# 1.net
KiCad netlist of a schematic drawn in EAGLE
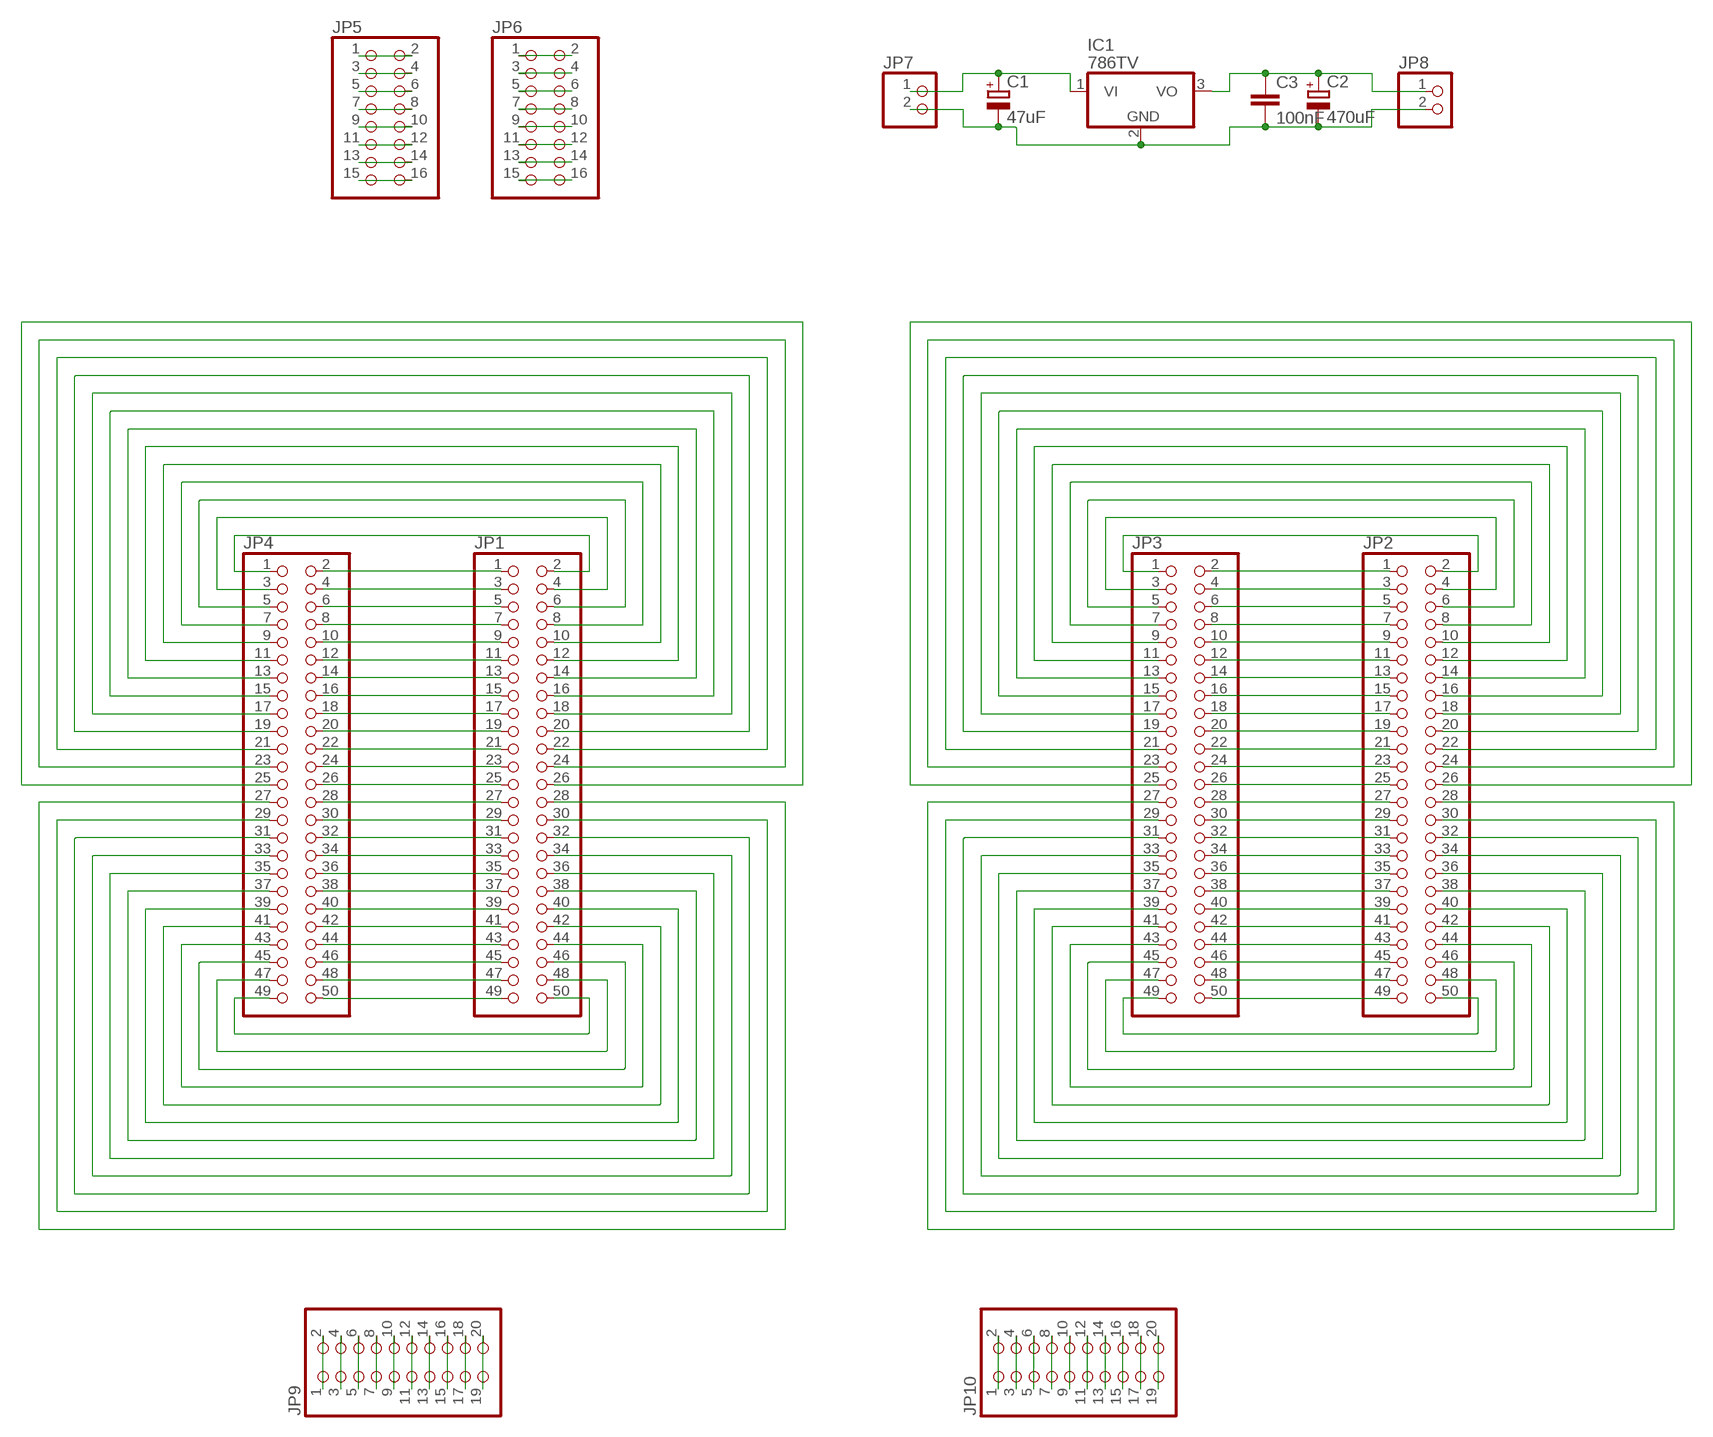
[diagram p0: schematic, sheet 1]

(export (version "E")
  (design (tool "Eeschema 10.0.6"))
  (components
    (comp (ref "C1")
      (value "47uF")
      (footprint "eagle-import:153CLV-0405")
      (libsource (lib "eagle-import") (part "CPOL-EU153CLV-0405"))
    )
    (comp (ref "C2")
      (value "470uF")
      (footprint "eagle-import:153CLV-0405")
      (libsource (lib "eagle-import") (part "CPOL-EU153CLV-0405"))
    )
    (comp (ref "C3")
      (value "100nF")
      (footprint "eagle-import:C025-024X044")
      (libsource (lib "eagle-import") (part "C-EU025-024X044"))
    )
    (comp (ref "IC1")
      (value "786TV")
      (footprint "eagle-import:TO220V")
      (libsource (lib "eagle-import") (part "78TV6"))
    )
    (comp (ref "JP1")
      (value "PINHD-2X25")
      (footprint "eagle-import:2X25")
      (libsource (lib "eagle-import") (part "PINHD-2X25"))
    )
    (comp (ref "JP2")
      (value "PINHD-2X25")
      (footprint "eagle-import:2X25")
      (libsource (lib "eagle-import") (part "PINHD-2X25"))
    )
    (comp (ref "JP3")
      (value "PINHD-2X25")
      (footprint "eagle-import:2X25")
      (libsource (lib "eagle-import") (part "PINHD-2X25"))
    )
    (comp (ref "JP4")
      (value "PINHD-2X25")
      (footprint "eagle-import:2X25")
      (libsource (lib "eagle-import") (part "PINHD-2X25"))
    )
    (comp (ref "JP5")
      (value "PINHD-2X8")
      (footprint "eagle-import:2X08")
      (libsource (lib "eagle-import") (part "PINHD-2X8"))
    )
    (comp (ref "JP6")
      (value "PINHD-2X8")
      (footprint "eagle-import:2X08")
      (libsource (lib "eagle-import") (part "PINHD-2X8"))
    )
    (comp (ref "JP7")
      (value "PINHD-1X2")
      (footprint "eagle-import:1X02")
      (libsource (lib "eagle-import") (part "PINHD-1X2"))
    )
    (comp (ref "JP8")
      (value "PINHD-1X2")
      (footprint "eagle-import:1X02")
      (libsource (lib "eagle-import") (part "PINHD-1X2"))
    )
    (comp (ref "JP9")
      (value "PINHD-2X10")
      (footprint "eagle-import:2X10")
      (libsource (lib "eagle-import") (part "PINHD-2X10"))
    )
    (comp (ref "JP10")
      (value "PINHD-2X10")
      (footprint "eagle-import:2X10")
      (libsource (lib "eagle-import") (part "PINHD-2X10"))
    )
  )
  (nets
    (net (code "1") (name "Net-(IC1-GND)") (class "Default")
      (node (ref "C1") (pin "-") (pinfunction "-_-") (pintype "passive"))
      (node (ref "C2") (pin "-") (pinfunction "-_-") (pintype "passive"))
      (node (ref "C3") (pin "2") (pinfunction "2_2") (pintype "passive"))
      (node (ref "IC1") (pin "2") (pinfunction "GND_2") (pintype "passive"))
      (node (ref "JP7") (pin "2") (pinfunction "2_2") (pintype "passive"))
      (node (ref "JP8") (pin "2") (pinfunction "2_2") (pintype "passive"))
    )
    (net (code "2") (name "Net-(IC1-VI)") (class "Default")
      (node (ref "C1") (pin "+") (pinfunction "+_+") (pintype "passive"))
      (node (ref "IC1") (pin "1") (pinfunction "VI_1") (pintype "input"))
      (node (ref "JP7") (pin "1") (pinfunction "1_1") (pintype "passive"))
    )
    (net (code "3") (name "Net-(IC1-VO)") (class "Default")
      (node (ref "C2") (pin "+") (pinfunction "+_+") (pintype "passive"))
      (node (ref "C3") (pin "1") (pinfunction "1_1") (pintype "passive"))
      (node (ref "IC1") (pin "3") (pinfunction "VO_3") (pintype "passive"))
      (node (ref "JP8") (pin "1") (pinfunction "1_1") (pintype "passive"))
    )
    (net (code "4") (name "Net-(JP1-Pad1)") (class "Default")
      (node (ref "JP1") (pin "1") (pinfunction "1_1") (pintype "passive"))
      (node (ref "JP4") (pin "2") (pinfunction "2_2") (pintype "passive"))
    )
    (net (code "5") (name "Net-(JP1-Pad2)") (class "Default")
      (node (ref "JP1") (pin "2") (pinfunction "2_2") (pintype "passive"))
      (node (ref "JP4") (pin "1") (pinfunction "1_1") (pintype "passive"))
    )
    (net (code "6") (name "Net-(JP1-Pad3)") (class "Default")
      (node (ref "JP1") (pin "3") (pinfunction "3_3") (pintype "passive"))
      (node (ref "JP4") (pin "4") (pinfunction "4_4") (pintype "passive"))
    )
    (net (code "7") (name "Net-(JP1-Pad4)") (class "Default")
      (node (ref "JP1") (pin "4") (pinfunction "4_4") (pintype "passive"))
      (node (ref "JP4") (pin "3") (pinfunction "3_3") (pintype "passive"))
    )
    (net (code "8") (name "Net-(JP1-Pad5)") (class "Default")
      (node (ref "JP1") (pin "5") (pinfunction "5_5") (pintype "passive"))
      (node (ref "JP4") (pin "6") (pinfunction "6_6") (pintype "passive"))
    )
    (net (code "9") (name "Net-(JP1-Pad6)") (class "Default")
      (node (ref "JP1") (pin "6") (pinfunction "6_6") (pintype "passive"))
      (node (ref "JP4") (pin "5") (pinfunction "5_5") (pintype "passive"))
    )
    (net (code "10") (name "Net-(JP1-Pad7)") (class "Default")
      (node (ref "JP1") (pin "7") (pinfunction "7_7") (pintype "passive"))
      (node (ref "JP4") (pin "8") (pinfunction "8_8") (pintype "passive"))
    )
    (net (code "11") (name "Net-(JP1-Pad8)") (class "Default")
      (node (ref "JP1") (pin "8") (pinfunction "8_8") (pintype "passive"))
      (node (ref "JP4") (pin "7") (pinfunction "7_7") (pintype "passive"))
    )
    (net (code "12") (name "Net-(JP1-Pad9)") (class "Default")
      (node (ref "JP1") (pin "9") (pinfunction "9_9") (pintype "passive"))
      (node (ref "JP4") (pin "10") (pinfunction "10_10") (pintype "passive"))
    )
    (net (code "13") (name "Net-(JP1-Pad10)") (class "Default")
      (node (ref "JP1") (pin "10") (pinfunction "10_10") (pintype "passive"))
      (node (ref "JP4") (pin "9") (pinfunction "9_9") (pintype "passive"))
    )
    (net (code "14") (name "Net-(JP1-Pad11)") (class "Default")
      (node (ref "JP1") (pin "11") (pinfunction "11_11") (pintype "passive"))
      (node (ref "JP4") (pin "12") (pinfunction "12_12") (pintype "passive"))
    )
    (net (code "15") (name "Net-(JP1-Pad12)") (class "Default")
      (node (ref "JP1") (pin "12") (pinfunction "12_12") (pintype "passive"))
      (node (ref "JP4") (pin "11") (pinfunction "11_11") (pintype "passive"))
    )
    (net (code "16") (name "Net-(JP1-Pad13)") (class "Default")
      (node (ref "JP1") (pin "13") (pinfunction "13_13") (pintype "passive"))
      (node (ref "JP4") (pin "14") (pinfunction "14_14") (pintype "passive"))
    )
    (net (code "17") (name "Net-(JP1-Pad14)") (class "Default")
      (node (ref "JP1") (pin "14") (pinfunction "14_14") (pintype "passive"))
      (node (ref "JP4") (pin "13") (pinfunction "13_13") (pintype "passive"))
    )
    (net (code "18") (name "Net-(JP1-Pad15)") (class "Default")
      (node (ref "JP1") (pin "15") (pinfunction "15_15") (pintype "passive"))
      (node (ref "JP4") (pin "16") (pinfunction "16_16") (pintype "passive"))
    )
    (net (code "19") (name "Net-(JP1-Pad16)") (class "Default")
      (node (ref "JP1") (pin "16") (pinfunction "16_16") (pintype "passive"))
      (node (ref "JP4") (pin "15") (pinfunction "15_15") (pintype "passive"))
    )
    (net (code "20") (name "Net-(JP1-Pad17)") (class "Default")
      (node (ref "JP1") (pin "17") (pinfunction "17_17") (pintype "passive"))
      (node (ref "JP4") (pin "18") (pinfunction "18_18") (pintype "passive"))
    )
    (net (code "21") (name "Net-(JP1-Pad18)") (class "Default")
      (node (ref "JP1") (pin "18") (pinfunction "18_18") (pintype "passive"))
      (node (ref "JP4") (pin "17") (pinfunction "17_17") (pintype "passive"))
    )
    (net (code "22") (name "Net-(JP1-Pad19)") (class "Default")
      (node (ref "JP1") (pin "19") (pinfunction "19_19") (pintype "passive"))
      (node (ref "JP4") (pin "20") (pinfunction "20_20") (pintype "passive"))
    )
    (net (code "23") (name "Net-(JP1-Pad20)") (class "Default")
      (node (ref "JP1") (pin "20") (pinfunction "20_20") (pintype "passive"))
      (node (ref "JP4") (pin "19") (pinfunction "19_19") (pintype "passive"))
    )
    (net (code "24") (name "Net-(JP1-Pad21)") (class "Default")
      (node (ref "JP1") (pin "21") (pinfunction "21_21") (pintype "passive"))
      (node (ref "JP4") (pin "22") (pinfunction "22_22") (pintype "passive"))
    )
    (net (code "25") (name "Net-(JP1-Pad22)") (class "Default")
      (node (ref "JP1") (pin "22") (pinfunction "22_22") (pintype "passive"))
      (node (ref "JP4") (pin "21") (pinfunction "21_21") (pintype "passive"))
    )
    (net (code "26") (name "Net-(JP1-Pad23)") (class "Default")
      (node (ref "JP1") (pin "23") (pinfunction "23_23") (pintype "passive"))
      (node (ref "JP4") (pin "24") (pinfunction "24_24") (pintype "passive"))
    )
    (net (code "27") (name "Net-(JP1-Pad24)") (class "Default")
      (node (ref "JP1") (pin "24") (pinfunction "24_24") (pintype "passive"))
      (node (ref "JP4") (pin "23") (pinfunction "23_23") (pintype "passive"))
    )
    (net (code "28") (name "Net-(JP1-Pad25)") (class "Default")
      (node (ref "JP1") (pin "25") (pinfunction "25_25") (pintype "passive"))
      (node (ref "JP4") (pin "26") (pinfunction "26_26") (pintype "passive"))
    )
    (net (code "29") (name "Net-(JP1-Pad26)") (class "Default")
      (node (ref "JP1") (pin "26") (pinfunction "26_26") (pintype "passive"))
      (node (ref "JP4") (pin "25") (pinfunction "25_25") (pintype "passive"))
    )
    (net (code "30") (name "Net-(JP1-Pad27)") (class "Default")
      (node (ref "JP1") (pin "27") (pinfunction "27_27") (pintype "passive"))
      (node (ref "JP4") (pin "28") (pinfunction "28_28") (pintype "passive"))
    )
    (net (code "31") (name "Net-(JP1-Pad28)") (class "Default")
      (node (ref "JP1") (pin "28") (pinfunction "28_28") (pintype "passive"))
      (node (ref "JP4") (pin "27") (pinfunction "27_27") (pintype "passive"))
    )
    (net (code "32") (name "Net-(JP1-Pad29)") (class "Default")
      (node (ref "JP1") (pin "29") (pinfunction "29_29") (pintype "passive"))
      (node (ref "JP4") (pin "30") (pinfunction "30_30") (pintype "passive"))
    )
    (net (code "33") (name "Net-(JP1-Pad30)") (class "Default")
      (node (ref "JP1") (pin "30") (pinfunction "30_30") (pintype "passive"))
      (node (ref "JP4") (pin "29") (pinfunction "29_29") (pintype "passive"))
    )
    (net (code "34") (name "Net-(JP1-Pad31)") (class "Default")
      (node (ref "JP1") (pin "31") (pinfunction "31_31") (pintype "passive"))
      (node (ref "JP4") (pin "32") (pinfunction "32_32") (pintype "passive"))
    )
    (net (code "35") (name "Net-(JP1-Pad32)") (class "Default")
      (node (ref "JP1") (pin "32") (pinfunction "32_32") (pintype "passive"))
      (node (ref "JP4") (pin "31") (pinfunction "31_31") (pintype "passive"))
    )
    (net (code "36") (name "Net-(JP1-Pad33)") (class "Default")
      (node (ref "JP1") (pin "33") (pinfunction "33_33") (pintype "passive"))
      (node (ref "JP4") (pin "34") (pinfunction "34_34") (pintype "passive"))
    )
    (net (code "37") (name "Net-(JP1-Pad34)") (class "Default")
      (node (ref "JP1") (pin "34") (pinfunction "34_34") (pintype "passive"))
      (node (ref "JP4") (pin "33") (pinfunction "33_33") (pintype "passive"))
    )
    (net (code "38") (name "Net-(JP1-Pad35)") (class "Default")
      (node (ref "JP1") (pin "35") (pinfunction "35_35") (pintype "passive"))
      (node (ref "JP4") (pin "36") (pinfunction "36_36") (pintype "passive"))
    )
    (net (code "39") (name "Net-(JP1-Pad36)") (class "Default")
      (node (ref "JP1") (pin "36") (pinfunction "36_36") (pintype "passive"))
      (node (ref "JP4") (pin "35") (pinfunction "35_35") (pintype "passive"))
    )
    (net (code "40") (name "Net-(JP1-Pad37)") (class "Default")
      (node (ref "JP1") (pin "37") (pinfunction "37_37") (pintype "passive"))
      (node (ref "JP4") (pin "38") (pinfunction "38_38") (pintype "passive"))
    )
    (net (code "41") (name "Net-(JP1-Pad38)") (class "Default")
      (node (ref "JP1") (pin "38") (pinfunction "38_38") (pintype "passive"))
      (node (ref "JP4") (pin "37") (pinfunction "37_37") (pintype "passive"))
    )
    (net (code "42") (name "Net-(JP1-Pad39)") (class "Default")
      (node (ref "JP1") (pin "39") (pinfunction "39_39") (pintype "passive"))
      (node (ref "JP4") (pin "40") (pinfunction "40_40") (pintype "passive"))
    )
    (net (code "43") (name "Net-(JP1-Pad40)") (class "Default")
      (node (ref "JP1") (pin "40") (pinfunction "40_40") (pintype "passive"))
      (node (ref "JP4") (pin "39") (pinfunction "39_39") (pintype "passive"))
    )
    (net (code "44") (name "Net-(JP1-Pad41)") (class "Default")
      (node (ref "JP1") (pin "41") (pinfunction "41_41") (pintype "passive"))
      (node (ref "JP4") (pin "42") (pinfunction "42_42") (pintype "passive"))
    )
    (net (code "45") (name "Net-(JP1-Pad42)") (class "Default")
      (node (ref "JP1") (pin "42") (pinfunction "42_42") (pintype "passive"))
      (node (ref "JP4") (pin "41") (pinfunction "41_41") (pintype "passive"))
    )
    (net (code "46") (name "Net-(JP1-Pad43)") (class "Default")
      (node (ref "JP1") (pin "43") (pinfunction "43_43") (pintype "passive"))
      (node (ref "JP4") (pin "44") (pinfunction "44_44") (pintype "passive"))
    )
    (net (code "47") (name "Net-(JP1-Pad44)") (class "Default")
      (node (ref "JP1") (pin "44") (pinfunction "44_44") (pintype "passive"))
      (node (ref "JP4") (pin "43") (pinfunction "43_43") (pintype "passive"))
    )
    (net (code "48") (name "Net-(JP1-Pad45)") (class "Default")
      (node (ref "JP1") (pin "45") (pinfunction "45_45") (pintype "passive"))
      (node (ref "JP4") (pin "46") (pinfunction "46_46") (pintype "passive"))
    )
    (net (code "49") (name "Net-(JP1-Pad46)") (class "Default")
      (node (ref "JP1") (pin "46") (pinfunction "46_46") (pintype "passive"))
      (node (ref "JP4") (pin "45") (pinfunction "45_45") (pintype "passive"))
    )
    (net (code "50") (name "Net-(JP1-Pad47)") (class "Default")
      (node (ref "JP1") (pin "47") (pinfunction "47_47") (pintype "passive"))
      (node (ref "JP4") (pin "48") (pinfunction "48_48") (pintype "passive"))
    )
    (net (code "51") (name "Net-(JP1-Pad48)") (class "Default")
      (node (ref "JP1") (pin "48") (pinfunction "48_48") (pintype "passive"))
      (node (ref "JP4") (pin "47") (pinfunction "47_47") (pintype "passive"))
    )
    (net (code "52") (name "Net-(JP1-Pad49)") (class "Default")
      (node (ref "JP1") (pin "49") (pinfunction "49_49") (pintype "passive"))
      (node (ref "JP4") (pin "50") (pinfunction "50_50") (pintype "passive"))
    )
    (net (code "53") (name "Net-(JP1-Pad50)") (class "Default")
      (node (ref "JP1") (pin "50") (pinfunction "50_50") (pintype "passive"))
      (node (ref "JP4") (pin "49") (pinfunction "49_49") (pintype "passive"))
    )
    (net (code "54") (name "Net-(JP2-Pad1)") (class "Default")
      (node (ref "JP2") (pin "1") (pinfunction "1_1") (pintype "passive"))
      (node (ref "JP3") (pin "2") (pinfunction "2_2") (pintype "passive"))
    )
    (net (code "55") (name "Net-(JP2-Pad2)") (class "Default")
      (node (ref "JP2") (pin "2") (pinfunction "2_2") (pintype "passive"))
      (node (ref "JP3") (pin "1") (pinfunction "1_1") (pintype "passive"))
    )
    (net (code "56") (name "Net-(JP2-Pad3)") (class "Default")
      (node (ref "JP2") (pin "3") (pinfunction "3_3") (pintype "passive"))
      (node (ref "JP3") (pin "4") (pinfunction "4_4") (pintype "passive"))
    )
    (net (code "57") (name "Net-(JP2-Pad4)") (class "Default")
      (node (ref "JP2") (pin "4") (pinfunction "4_4") (pintype "passive"))
      (node (ref "JP3") (pin "3") (pinfunction "3_3") (pintype "passive"))
    )
    (net (code "58") (name "Net-(JP2-Pad5)") (class "Default")
      (node (ref "JP2") (pin "5") (pinfunction "5_5") (pintype "passive"))
      (node (ref "JP3") (pin "6") (pinfunction "6_6") (pintype "passive"))
    )
    (net (code "59") (name "Net-(JP2-Pad6)") (class "Default")
      (node (ref "JP2") (pin "6") (pinfunction "6_6") (pintype "passive"))
      (node (ref "JP3") (pin "5") (pinfunction "5_5") (pintype "passive"))
    )
    (net (code "60") (name "Net-(JP2-Pad7)") (class "Default")
      (node (ref "JP2") (pin "7") (pinfunction "7_7") (pintype "passive"))
      (node (ref "JP3") (pin "8") (pinfunction "8_8") (pintype "passive"))
    )
    (net (code "61") (name "Net-(JP2-Pad8)") (class "Default")
      (node (ref "JP2") (pin "8") (pinfunction "8_8") (pintype "passive"))
      (node (ref "JP3") (pin "7") (pinfunction "7_7") (pintype "passive"))
    )
    (net (code "62") (name "Net-(JP2-Pad9)") (class "Default")
      (node (ref "JP2") (pin "9") (pinfunction "9_9") (pintype "passive"))
      (node (ref "JP3") (pin "10") (pinfunction "10_10") (pintype "passive"))
    )
    (net (code "63") (name "Net-(JP2-Pad10)") (class "Default")
      (node (ref "JP2") (pin "10") (pinfunction "10_10") (pintype "passive"))
      (node (ref "JP3") (pin "9") (pinfunction "9_9") (pintype "passive"))
    )
    (net (code "64") (name "Net-(JP2-Pad11)") (class "Default")
      (node (ref "JP2") (pin "11") (pinfunction "11_11") (pintype "passive"))
      (node (ref "JP3") (pin "12") (pinfunction "12_12") (pintype "passive"))
    )
    (net (code "65") (name "Net-(JP2-Pad12)") (class "Default")
      (node (ref "JP2") (pin "12") (pinfunction "12_12") (pintype "passive"))
      (node (ref "JP3") (pin "11") (pinfunction "11_11") (pintype "passive"))
    )
    (net (code "66") (name "Net-(JP2-Pad13)") (class "Default")
      (node (ref "JP2") (pin "13") (pinfunction "13_13") (pintype "passive"))
      (node (ref "JP3") (pin "14") (pinfunction "14_14") (pintype "passive"))
    )
    (net (code "67") (name "Net-(JP2-Pad14)") (class "Default")
      (node (ref "JP2") (pin "14") (pinfunction "14_14") (pintype "passive"))
      (node (ref "JP3") (pin "13") (pinfunction "13_13") (pintype "passive"))
    )
    (net (code "68") (name "Net-(JP2-Pad15)") (class "Default")
      (node (ref "JP2") (pin "15") (pinfunction "15_15") (pintype "passive"))
      (node (ref "JP3") (pin "16") (pinfunction "16_16") (pintype "passive"))
    )
    (net (code "69") (name "Net-(JP2-Pad16)") (class "Default")
      (node (ref "JP2") (pin "16") (pinfunction "16_16") (pintype "passive"))
      (node (ref "JP3") (pin "15") (pinfunction "15_15") (pintype "passive"))
    )
    (net (code "70") (name "Net-(JP2-Pad17)") (class "Default")
      (node (ref "JP2") (pin "17") (pinfunction "17_17") (pintype "passive"))
      (node (ref "JP3") (pin "18") (pinfunction "18_18") (pintype "passive"))
    )
    (net (code "71") (name "Net-(JP2-Pad18)") (class "Default")
      (node (ref "JP2") (pin "18") (pinfunction "18_18") (pintype "passive"))
      (node (ref "JP3") (pin "17") (pinfunction "17_17") (pintype "passive"))
    )
    (net (code "72") (name "Net-(JP2-Pad19)") (class "Default")
      (node (ref "JP2") (pin "19") (pinfunction "19_19") (pintype "passive"))
      (node (ref "JP3") (pin "20") (pinfunction "20_20") (pintype "passive"))
    )
    (net (code "73") (name "Net-(JP2-Pad20)") (class "Default")
      (node (ref "JP2") (pin "20") (pinfunction "20_20") (pintype "passive"))
      (node (ref "JP3") (pin "19") (pinfunction "19_19") (pintype "passive"))
    )
    (net (code "74") (name "Net-(JP2-Pad21)") (class "Default")
      (node (ref "JP2") (pin "21") (pinfunction "21_21") (pintype "passive"))
      (node (ref "JP3") (pin "22") (pinfunction "22_22") (pintype "passive"))
    )
    (net (code "75") (name "Net-(JP2-Pad22)") (class "Default")
      (node (ref "JP2") (pin "22") (pinfunction "22_22") (pintype "passive"))
      (node (ref "JP3") (pin "21") (pinfunction "21_21") (pintype "passive"))
    )
    (net (code "76") (name "Net-(JP2-Pad23)") (class "Default")
      (node (ref "JP2") (pin "23") (pinfunction "23_23") (pintype "passive"))
      (node (ref "JP3") (pin "24") (pinfunction "24_24") (pintype "passive"))
    )
    (net (code "77") (name "Net-(JP2-Pad24)") (class "Default")
      (node (ref "JP2") (pin "24") (pinfunction "24_24") (pintype "passive"))
      (node (ref "JP3") (pin "23") (pinfunction "23_23") (pintype "passive"))
    )
    (net (code "78") (name "Net-(JP2-Pad25)") (class "Default")
      (node (ref "JP2") (pin "25") (pinfunction "25_25") (pintype "passive"))
      (node (ref "JP3") (pin "26") (pinfunction "26_26") (pintype "passive"))
    )
    (net (code "79") (name "Net-(JP2-Pad26)") (class "Default")
      (node (ref "JP2") (pin "26") (pinfunction "26_26") (pintype "passive"))
      (node (ref "JP3") (pin "25") (pinfunction "25_25") (pintype "passive"))
    )
    (net (code "80") (name "Net-(JP2-Pad27)") (class "Default")
      (node (ref "JP2") (pin "27") (pinfunction "27_27") (pintype "passive"))
      (node (ref "JP3") (pin "28") (pinfunction "28_28") (pintype "passive"))
    )
    (net (code "81") (name "Net-(JP2-Pad28)") (class "Default")
      (node (ref "JP2") (pin "28") (pinfunction "28_28") (pintype "passive"))
      (node (ref "JP3") (pin "27") (pinfunction "27_27") (pintype "passive"))
    )
    (net (code "82") (name "Net-(JP2-Pad29)") (class "Default")
      (node (ref "JP2") (pin "29") (pinfunction "29_29") (pintype "passive"))
      (node (ref "JP3") (pin "30") (pinfunction "30_30") (pintype "passive"))
    )
    (net (code "83") (name "Net-(JP2-Pad30)") (class "Default")
      (node (ref "JP2") (pin "30") (pinfunction "30_30") (pintype "passive"))
      (node (ref "JP3") (pin "29") (pinfunction "29_29") (pintype "passive"))
    )
    (net (code "84") (name "Net-(JP2-Pad31)") (class "Default")
      (node (ref "JP2") (pin "31") (pinfunction "31_31") (pintype "passive"))
      (node (ref "JP3") (pin "32") (pinfunction "32_32") (pintype "passive"))
    )
    (net (code "85") (name "Net-(JP2-Pad32)") (class "Default")
      (node (ref "JP2") (pin "32") (pinfunction "32_32") (pintype "passive"))
      (node (ref "JP3") (pin "31") (pinfunction "31_31") (pintype "passive"))
    )
    (net (code "86") (name "Net-(JP2-Pad33)") (class "Default")
      (node (ref "JP2") (pin "33") (pinfunction "33_33") (pintype "passive"))
      (node (ref "JP3") (pin "34") (pinfunction "34_34") (pintype "passive"))
    )
    (net (code "87") (name "Net-(JP2-Pad34)") (class "Default")
      (node (ref "JP2") (pin "34") (pinfunction "34_34") (pintype "passive"))
      (node (ref "JP3") (pin "33") (pinfunction "33_33") (pintype "passive"))
    )
    (net (code "88") (name "Net-(JP2-Pad35)") (class "Default")
      (node (ref "JP2") (pin "35") (pinfunction "35_35") (pintype "passive"))
      (node (ref "JP3") (pin "36") (pinfunction "36_36") (pintype "passive"))
    )
    (net (code "89") (name "Net-(JP2-Pad36)") (class "Default")
      (node (ref "JP2") (pin "36") (pinfunction "36_36") (pintype "passive"))
      (node (ref "JP3") (pin "35") (pinfunction "35_35") (pintype "passive"))
    )
    (net (code "90") (name "Net-(JP2-Pad37)") (class "Default")
      (node (ref "JP2") (pin "37") (pinfunction "37_37") (pintype "passive"))
      (node (ref "JP3") (pin "38") (pinfunction "38_38") (pintype "passive"))
    )
    (net (code "91") (name "Net-(JP2-Pad38)") (class "Default")
      (node (ref "JP2") (pin "38") (pinfunction "38_38") (pintype "passive"))
      (node (ref "JP3") (pin "37") (pinfunction "37_37") (pintype "passive"))
    )
    (net (code "92") (name "Net-(JP2-Pad39)") (class "Default")
      (node (ref "JP2") (pin "39") (pinfunction "39_39") (pintype "passive"))
      (node (ref "JP3") (pin "40") (pinfunction "40_40") (pintype "passive"))
    )
    (net (code "93") (name "Net-(JP2-Pad40)") (class "Default")
      (node (ref "JP2") (pin "40") (pinfunction "40_40") (pintype "passive"))
      (node (ref "JP3") (pin "39") (pinfunction "39_39") (pintype "passive"))
    )
    (net (code "94") (name "Net-(JP2-Pad41)") (class "Default")
      (node (ref "JP2") (pin "41") (pinfunction "41_41") (pintype "passive"))
      (node (ref "JP3") (pin "42") (pinfunction "42_42") (pintype "passive"))
    )
    (net (code "95") (name "Net-(JP2-Pad42)") (class "Default")
      (node (ref "JP2") (pin "42") (pinfunction "42_42") (pintype "passive"))
      (node (ref "JP3") (pin "41") (pinfunction "41_41") (pintype "passive"))
    )
    (net (code "96") (name "Net-(JP2-Pad43)") (class "Default")
      (node (ref "JP2") (pin "43") (pinfunction "43_43") (pintype "passive"))
      (node (ref "JP3") (pin "44") (pinfunction "44_44") (pintype "passive"))
    )
    (net (code "97") (name "Net-(JP2-Pad44)") (class "Default")
      (node (ref "JP2") (pin "44") (pinfunction "44_44") (pintype "passive"))
      (node (ref "JP3") (pin "43") (pinfunction "43_43") (pintype "passive"))
    )
    (net (code "98") (name "Net-(JP2-Pad45)") (class "Default")
      (node (ref "JP2") (pin "45") (pinfunction "45_45") (pintype "passive"))
      (node (ref "JP3") (pin "46") (pinfunction "46_46") (pintype "passive"))
    )
    (net (code "99") (name "Net-(JP2-Pad46)") (class "Default")
      (node (ref "JP2") (pin "46") (pinfunction "46_46") (pintype "passive"))
      (node (ref "JP3") (pin "45") (pinfunction "45_45") (pintype "passive"))
    )
    (net (code "100") (name "Net-(JP2-Pad47)") (class "Default")
      (node (ref "JP2") (pin "47") (pinfunction "47_47") (pintype "passive"))
      (node (ref "JP3") (pin "48") (pinfunction "48_48") (pintype "passive"))
    )
    (net (code "101") (name "Net-(JP2-Pad48)") (class "Default")
      (node (ref "JP2") (pin "48") (pinfunction "48_48") (pintype "passive"))
      (node (ref "JP3") (pin "47") (pinfunction "47_47") (pintype "passive"))
    )
    (net (code "102") (name "Net-(JP2-Pad49)") (class "Default")
      (node (ref "JP2") (pin "49") (pinfunction "49_49") (pintype "passive"))
      (node (ref "JP3") (pin "50") (pinfunction "50_50") (pintype "passive"))
    )
    (net (code "103") (name "Net-(JP2-Pad50)") (class "Default")
      (node (ref "JP2") (pin "50") (pinfunction "50_50") (pintype "passive"))
      (node (ref "JP3") (pin "49") (pinfunction "49_49") (pintype "passive"))
    )
    (net (code "104") (name "Net-(JP5-Pad1)") (class "Default")
      (node (ref "JP5") (pin "1") (pinfunction "1_1") (pintype "passive"))
      (node (ref "JP5") (pin "2") (pinfunction "2_2") (pintype "passive"))
    )
    (net (code "105") (name "Net-(JP5-Pad3)") (class "Default")
      (node (ref "JP5") (pin "3") (pinfunction "3_3") (pintype "passive"))
      (node (ref "JP5") (pin "4") (pinfunction "4_4") (pintype "passive"))
    )
    (net (code "106") (name "Net-(JP5-Pad5)") (class "Default")
      (node (ref "JP5") (pin "5") (pinfunction "5_5") (pintype "passive"))
      (node (ref "JP5") (pin "6") (pinfunction "6_6") (pintype "passive"))
    )
    (net (code "107") (name "Net-(JP5-Pad7)") (class "Default")
      (node (ref "JP5") (pin "7") (pinfunction "7_7") (pintype "passive"))
      (node (ref "JP5") (pin "8") (pinfunction "8_8") (pintype "passive"))
    )
    (net (code "108") (name "Net-(JP5-Pad10)") (class "Default")
      (node (ref "JP5") (pin "10") (pinfunction "10_10") (pintype "passive"))
      (node (ref "JP5") (pin "9") (pinfunction "9_9") (pintype "passive"))
    )
    (net (code "109") (name "Net-(JP5-Pad11)") (class "Default")
      (node (ref "JP5") (pin "11") (pinfunction "11_11") (pintype "passive"))
      (node (ref "JP5") (pin "12") (pinfunction "12_12") (pintype "passive"))
    )
    (net (code "110") (name "Net-(JP5-Pad13)") (class "Default")
      (node (ref "JP5") (pin "13") (pinfunction "13_13") (pintype "passive"))
      (node (ref "JP5") (pin "14") (pinfunction "14_14") (pintype "passive"))
    )
    (net (code "111") (name "Net-(JP5-Pad15)") (class "Default")
      (node (ref "JP5") (pin "15") (pinfunction "15_15") (pintype "passive"))
      (node (ref "JP5") (pin "16") (pinfunction "16_16") (pintype "passive"))
    )
    (net (code "112") (name "Net-(JP6-Pad1)") (class "Default")
      (node (ref "JP6") (pin "1") (pinfunction "1_1") (pintype "passive"))
      (node (ref "JP6") (pin "2") (pinfunction "2_2") (pintype "passive"))
    )
    (net (code "113") (name "Net-(JP6-Pad3)") (class "Default")
      (node (ref "JP6") (pin "3") (pinfunction "3_3") (pintype "passive"))
      (node (ref "JP6") (pin "4") (pinfunction "4_4") (pintype "passive"))
    )
    (net (code "114") (name "Net-(JP6-Pad5)") (class "Default")
      (node (ref "JP6") (pin "5") (pinfunction "5_5") (pintype "passive"))
      (node (ref "JP6") (pin "6") (pinfunction "6_6") (pintype "passive"))
    )
    (net (code "115") (name "Net-(JP6-Pad7)") (class "Default")
      (node (ref "JP6") (pin "7") (pinfunction "7_7") (pintype "passive"))
      (node (ref "JP6") (pin "8") (pinfunction "8_8") (pintype "passive"))
    )
    (net (code "116") (name "Net-(JP6-Pad10)") (class "Default")
      (node (ref "JP6") (pin "10") (pinfunction "10_10") (pintype "passive"))
      (node (ref "JP6") (pin "9") (pinfunction "9_9") (pintype "passive"))
    )
    (net (code "117") (name "Net-(JP6-Pad11)") (class "Default")
      (node (ref "JP6") (pin "11") (pinfunction "11_11") (pintype "passive"))
      (node (ref "JP6") (pin "12") (pinfunction "12_12") (pintype "passive"))
    )
    (net (code "118") (name "Net-(JP6-Pad13)") (class "Default")
      (node (ref "JP6") (pin "13") (pinfunction "13_13") (pintype "passive"))
      (node (ref "JP6") (pin "14") (pinfunction "14_14") (pintype "passive"))
    )
    (net (code "119") (name "Net-(JP6-Pad15)") (class "Default")
      (node (ref "JP6") (pin "15") (pinfunction "15_15") (pintype "passive"))
      (node (ref "JP6") (pin "16") (pinfunction "16_16") (pintype "passive"))
    )
    (net (code "120") (name "Net-(JP9-Pad1)") (class "Default")
      (node (ref "JP9") (pin "1") (pinfunction "1_1") (pintype "passive"))
      (node (ref "JP9") (pin "2") (pinfunction "2_2") (pintype "passive"))
    )
    (net (code "121") (name "Net-(JP9-Pad3)") (class "Default")
      (node (ref "JP9") (pin "3") (pinfunction "3_3") (pintype "passive"))
      (node (ref "JP9") (pin "4") (pinfunction "4_4") (pintype "passive"))
    )
    (net (code "122") (name "Net-(JP9-Pad5)") (class "Default")
      (node (ref "JP9") (pin "5") (pinfunction "5_5") (pintype "passive"))
      (node (ref "JP9") (pin "6") (pinfunction "6_6") (pintype "passive"))
    )
    (net (code "123") (name "Net-(JP9-Pad7)") (class "Default")
      (node (ref "JP9") (pin "7") (pinfunction "7_7") (pintype "passive"))
      (node (ref "JP9") (pin "8") (pinfunction "8_8") (pintype "passive"))
    )
    (net (code "124") (name "Net-(JP9-Pad10)") (class "Default")
      (node (ref "JP9") (pin "10") (pinfunction "10_10") (pintype "passive"))
      (node (ref "JP9") (pin "9") (pinfunction "9_9") (pintype "passive"))
    )
    (net (code "125") (name "Net-(JP9-Pad11)") (class "Default")
      (node (ref "JP9") (pin "11") (pinfunction "11_11") (pintype "passive"))
      (node (ref "JP9") (pin "12") (pinfunction "12_12") (pintype "passive"))
    )
    (net (code "126") (name "Net-(JP9-Pad13)") (class "Default")
      (node (ref "JP9") (pin "13") (pinfunction "13_13") (pintype "passive"))
      (node (ref "JP9") (pin "14") (pinfunction "14_14") (pintype "passive"))
    )
    (net (code "127") (name "Net-(JP9-Pad15)") (class "Default")
      (node (ref "JP9") (pin "15") (pinfunction "15_15") (pintype "passive"))
      (node (ref "JP9") (pin "16") (pinfunction "16_16") (pintype "passive"))
    )
    (net (code "128") (name "Net-(JP9-Pad17)") (class "Default")
      (node (ref "JP9") (pin "17") (pinfunction "17_17") (pintype "passive"))
      (node (ref "JP9") (pin "18") (pinfunction "18_18") (pintype "passive"))
    )
    (net (code "129") (name "Net-(JP9-Pad19)") (class "Default")
      (node (ref "JP9") (pin "19") (pinfunction "19_19") (pintype "passive"))
      (node (ref "JP9") (pin "20") (pinfunction "20_20") (pintype "passive"))
    )
    (net (code "130") (name "Net-(JP10-Pad1)") (class "Default")
      (node (ref "JP10") (pin "1") (pinfunction "1_1") (pintype "passive"))
      (node (ref "JP10") (pin "2") (pinfunction "2_2") (pintype "passive"))
    )
    (net (code "131") (name "Net-(JP10-Pad3)") (class "Default")
      (node (ref "JP10") (pin "3") (pinfunction "3_3") (pintype "passive"))
      (node (ref "JP10") (pin "4") (pinfunction "4_4") (pintype "passive"))
    )
    (net (code "132") (name "Net-(JP10-Pad5)") (class "Default")
      (node (ref "JP10") (pin "5") (pinfunction "5_5") (pintype "passive"))
      (node (ref "JP10") (pin "6") (pinfunction "6_6") (pintype "passive"))
    )
    (net (code "133") (name "Net-(JP10-Pad7)") (class "Default")
      (node (ref "JP10") (pin "7") (pinfunction "7_7") (pintype "passive"))
      (node (ref "JP10") (pin "8") (pinfunction "8_8") (pintype "passive"))
    )
    (net (code "134") (name "Net-(JP10-Pad10)") (class "Default")
      (node (ref "JP10") (pin "10") (pinfunction "10_10") (pintype "passive"))
      (node (ref "JP10") (pin "9") (pinfunction "9_9") (pintype "passive"))
    )
    (net (code "135") (name "Net-(JP10-Pad11)") (class "Default")
      (node (ref "JP10") (pin "11") (pinfunction "11_11") (pintype "passive"))
      (node (ref "JP10") (pin "12") (pinfunction "12_12") (pintype "passive"))
    )
    (net (code "136") (name "Net-(JP10-Pad13)") (class "Default")
      (node (ref "JP10") (pin "13") (pinfunction "13_13") (pintype "passive"))
      (node (ref "JP10") (pin "14") (pinfunction "14_14") (pintype "passive"))
    )
    (net (code "137") (name "Net-(JP10-Pad15)") (class "Default")
      (node (ref "JP10") (pin "15") (pinfunction "15_15") (pintype "passive"))
      (node (ref "JP10") (pin "16") (pinfunction "16_16") (pintype "passive"))
    )
    (net (code "138") (name "Net-(JP10-Pad17)") (class "Default")
      (node (ref "JP10") (pin "17") (pinfunction "17_17") (pintype "passive"))
      (node (ref "JP10") (pin "18") (pinfunction "18_18") (pintype "passive"))
    )
    (net (code "139") (name "Net-(JP10-Pad19)") (class "Default")
      (node (ref "JP10") (pin "19") (pinfunction "19_19") (pintype "passive"))
      (node (ref "JP10") (pin "20") (pinfunction "20_20") (pintype "passive"))
    )
  )
)
